# AuxilaryWiring.net
KiCad netlist of a schematic drawn in EAGLE
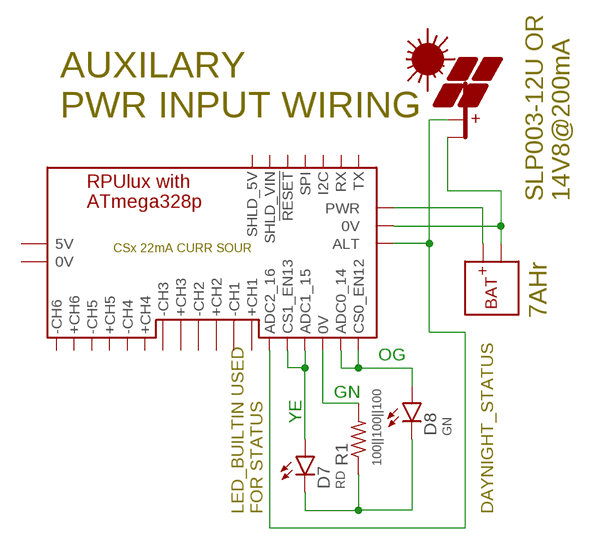
[diagram p0: schematic, sheet 1]

(export (version "E")
  (design (tool "Eeschema 10.0.6"))
  (components
    (comp (ref "D7")
      (value "RD")
      (footprint "eagle-import:LED5MM")
      (libsource (lib "eagle-import") (part "LED5MM"))
    )
    (comp (ref "D8")
      (value "GN")
      (footprint "eagle-import:LED5MM")
      (libsource (lib "eagle-import") (part "LED5MM"))
    )
    (comp (ref "PV4")
      (value "PV")
      (footprint "eagle-import:NA-30")
      (libsource (lib "eagle-import") (part "PV"))
    )
    (comp (ref "R1")
      (value "100||100||100")
      (footprint "eagle-import:C0805(2012)")
      (libsource (lib "eagle-import") (part "R0805"))
    )
    (comp (ref "U$1")
      (value "RPULUX")
      (footprint "eagle-import:WITH_RPU_NAMES")
      (libsource (lib "eagle-import") (part "RPULUX"))
    )
    (comp (ref "U$7")
      (value "BAT")
      (footprint "eagle-import:NA-30")
      (libsource (lib "eagle-import") (part "BAT"))
    )
  )
  (nets
    (net (code "1") (name "/GN") (class "Default")
      (node (ref "R1") (pin "2") (pinfunction "2_2") (pintype "passive"))
      (node (ref "U$1") (pin "0V@DIO2") (pinfunction "0V_0V@DIO2") (pintype "bidirectional"))
    )
    (net (code "2") (name "/OG") (class "Default")
      (node (ref "D8") (pin "A") (pinfunction "A_A") (pintype "passive"))
      (node (ref "U$1") (pin "22MA@ADC0") (pinfunction "CS0_EN12_22MA@ADC0") (pintype "bidirectional"))
      (node (ref "U$1") (pin "ADC0") (pinfunction "ADC0_14_ADC0") (pintype "bidirectional"))
    )
    (net (code "3") (name "/YE") (class "Default")
      (node (ref "D7") (pin "A") (pinfunction "A_A") (pintype "passive"))
      (node (ref "U$1") (pin "22MA@ADC1") (pinfunction "CS1_EN13_22MA@ADC1") (pintype "bidirectional"))
      (node (ref "U$1") (pin "ADC1") (pinfunction "ADC1_15_ADC1") (pintype "bidirectional"))
    )
    (net (code "4") (name "Net-(D7-PadK)") (class "Default")
      (node (ref "D7") (pin "K") (pinfunction "K_K") (pintype "passive"))
      (node (ref "D8") (pin "K") (pinfunction "K_K") (pintype "passive"))
      (node (ref "R1") (pin "1") (pinfunction "1_1") (pintype "passive"))
    )
    (net (code "5") (name "Net-(PV4-+PV)") (class "Default")
      (node (ref "PV4") (pin "1") (pinfunction "+PV_1") (pintype "bidirectional"))
      (node (ref "U$1") (pin "ADC2") (pinfunction "ADC2_16_ADC2") (pintype "bidirectional"))
      (node (ref "U$1") (pin "AUX") (pinfunction "ALT_AUX") (pintype "bidirectional"))
    )
    (net (code "6") (name "Net-(PV4--PV)") (class "Default")
      (node (ref "PV4") (pin "2") (pinfunction "-PV_2") (pintype "bidirectional"))
      (node (ref "U$1") (pin "0V@PWR") (pinfunction "0V_0V@PWR") (pintype "bidirectional"))
      (node (ref "U$7") (pin "2") (pinfunction "-BAT_2") (pintype "bidirectional"))
    )
    (net (code "7") (name "Net-(U$7-+BAT)") (class "Default")
      (node (ref "U$1") (pin "PWR") (pinfunction "PWR_PWR") (pintype "bidirectional"))
      (node (ref "U$7") (pin "1") (pinfunction "+BAT_1") (pintype "bidirectional"))
    )
    (net (code "8") (name "unconnected-(U$1-Pad+CH1)") (class "Default")
      (node (ref "U$1") (pin "+CH1") (pinfunction "+CH1_+CH1") (pintype "bidirectional"))
    )
    (net (code "9") (name "unconnected-(U$1-Pad+CH2)") (class "Default")
      (node (ref "U$1") (pin "+CH2") (pinfunction "+CH2_+CH2") (pintype "bidirectional"))
    )
    (net (code "10") (name "unconnected-(U$1-Pad+CH3)") (class "Default")
      (node (ref "U$1") (pin "+CH3") (pinfunction "+CH3_+CH3") (pintype "bidirectional"))
    )
    (net (code "11") (name "unconnected-(U$1-Pad+CH4)") (class "Default")
      (node (ref "U$1") (pin "+CH4") (pinfunction "+CH4_+CH4") (pintype "bidirectional"))
    )
    (net (code "12") (name "unconnected-(U$1-Pad+CH5)") (class "Default")
      (node (ref "U$1") (pin "+CH5") (pinfunction "+CH5_+CH5") (pintype "bidirectional"))
    )
    (net (code "13") (name "unconnected-(U$1-Pad+CH6)") (class "Default")
      (node (ref "U$1") (pin "+CH6") (pinfunction "+CH6_+CH6") (pintype "bidirectional"))
    )
    (net (code "14") (name "unconnected-(U$1-Pad-CH1)") (class "Default")
      (node (ref "U$1") (pin "-CH1") (pinfunction "-CH1_-CH1") (pintype "bidirectional"))
    )
    (net (code "15") (name "unconnected-(U$1-Pad-CH2)") (class "Default")
      (node (ref "U$1") (pin "-CH2") (pinfunction "-CH2_-CH2") (pintype "bidirectional"))
    )
    (net (code "16") (name "unconnected-(U$1-Pad-CH3)") (class "Default")
      (node (ref "U$1") (pin "-CH3") (pinfunction "-CH3_-CH3") (pintype "bidirectional"))
    )
    (net (code "17") (name "unconnected-(U$1-Pad-CH4)") (class "Default")
      (node (ref "U$1") (pin "-CH4") (pinfunction "-CH4_-CH4") (pintype "bidirectional"))
    )
    (net (code "18") (name "unconnected-(U$1-Pad-CH5)") (class "Default")
      (node (ref "U$1") (pin "-CH5") (pinfunction "-CH5_-CH5") (pintype "bidirectional"))
    )
    (net (code "19") (name "unconnected-(U$1-Pad-CH6)") (class "Default")
      (node (ref "U$1") (pin "-CH6") (pinfunction "-CH6_-CH6") (pintype "bidirectional"))
    )
    (net (code "20") (name "unconnected-(U$1-Pad0V)") (class "Default")
      (node (ref "U$1") (pin "0V") (pinfunction "0V_0V") (pintype "bidirectional"))
    )
    (net (code "21") (name "unconnected-(U$1-Pad5V)") (class "Default")
      (node (ref "U$1") (pin "5V") (pinfunction "5V_5V") (pintype "bidirectional"))
    )
    (net (code "22") (name "unconnected-(U$1-PadI2C)") (class "Default")
      (node (ref "U$1") (pin "I2C") (pinfunction "I2C_I2C") (pintype "bidirectional"))
    )
    (net (code "23") (name "unconnected-(U$1-PadRX)") (class "Default")
      (node (ref "U$1") (pin "RX") (pinfunction "RX_RX") (pintype "bidirectional"))
    )
    (net (code "24") (name "unconnected-(U$1-PadSHLD_5V)") (class "Default")
      (node (ref "U$1") (pin "SHLD_5V") (pinfunction "SHLD_5V_SHLD_5V") (pintype "bidirectional"))
    )
    (net (code "25") (name "unconnected-(U$1-PadSPI)") (class "Default")
      (node (ref "U$1") (pin "SPI") (pinfunction "SPI_SPI") (pintype "bidirectional"))
    )
    (net (code "26") (name "unconnected-(U$1-PadTX)") (class "Default")
      (node (ref "U$1") (pin "TX") (pinfunction "TX_TX") (pintype "bidirectional"))
    )
    (net (code "27") (name "unconnected-(U$1-SHLD_VIN-PadSHLD_VOUT)") (class "Default")
      (node (ref "U$1") (pin "SHLD_VOUT") (pinfunction "SHLD_VIN_SHLD_VOUT") (pintype "bidirectional"))
    )
    (net (code "28") (name "unconnected-(U$1-~{RESET}-Pad!RESET)") (class "Default")
      (node (ref "U$1") (pin "!RESET") (pinfunction "~{RESET}_!RESET") (pintype "bidirectional"))
    )
  )
)
